# M103X.net
KiCad netlist of a schematic drawn in EAGLE
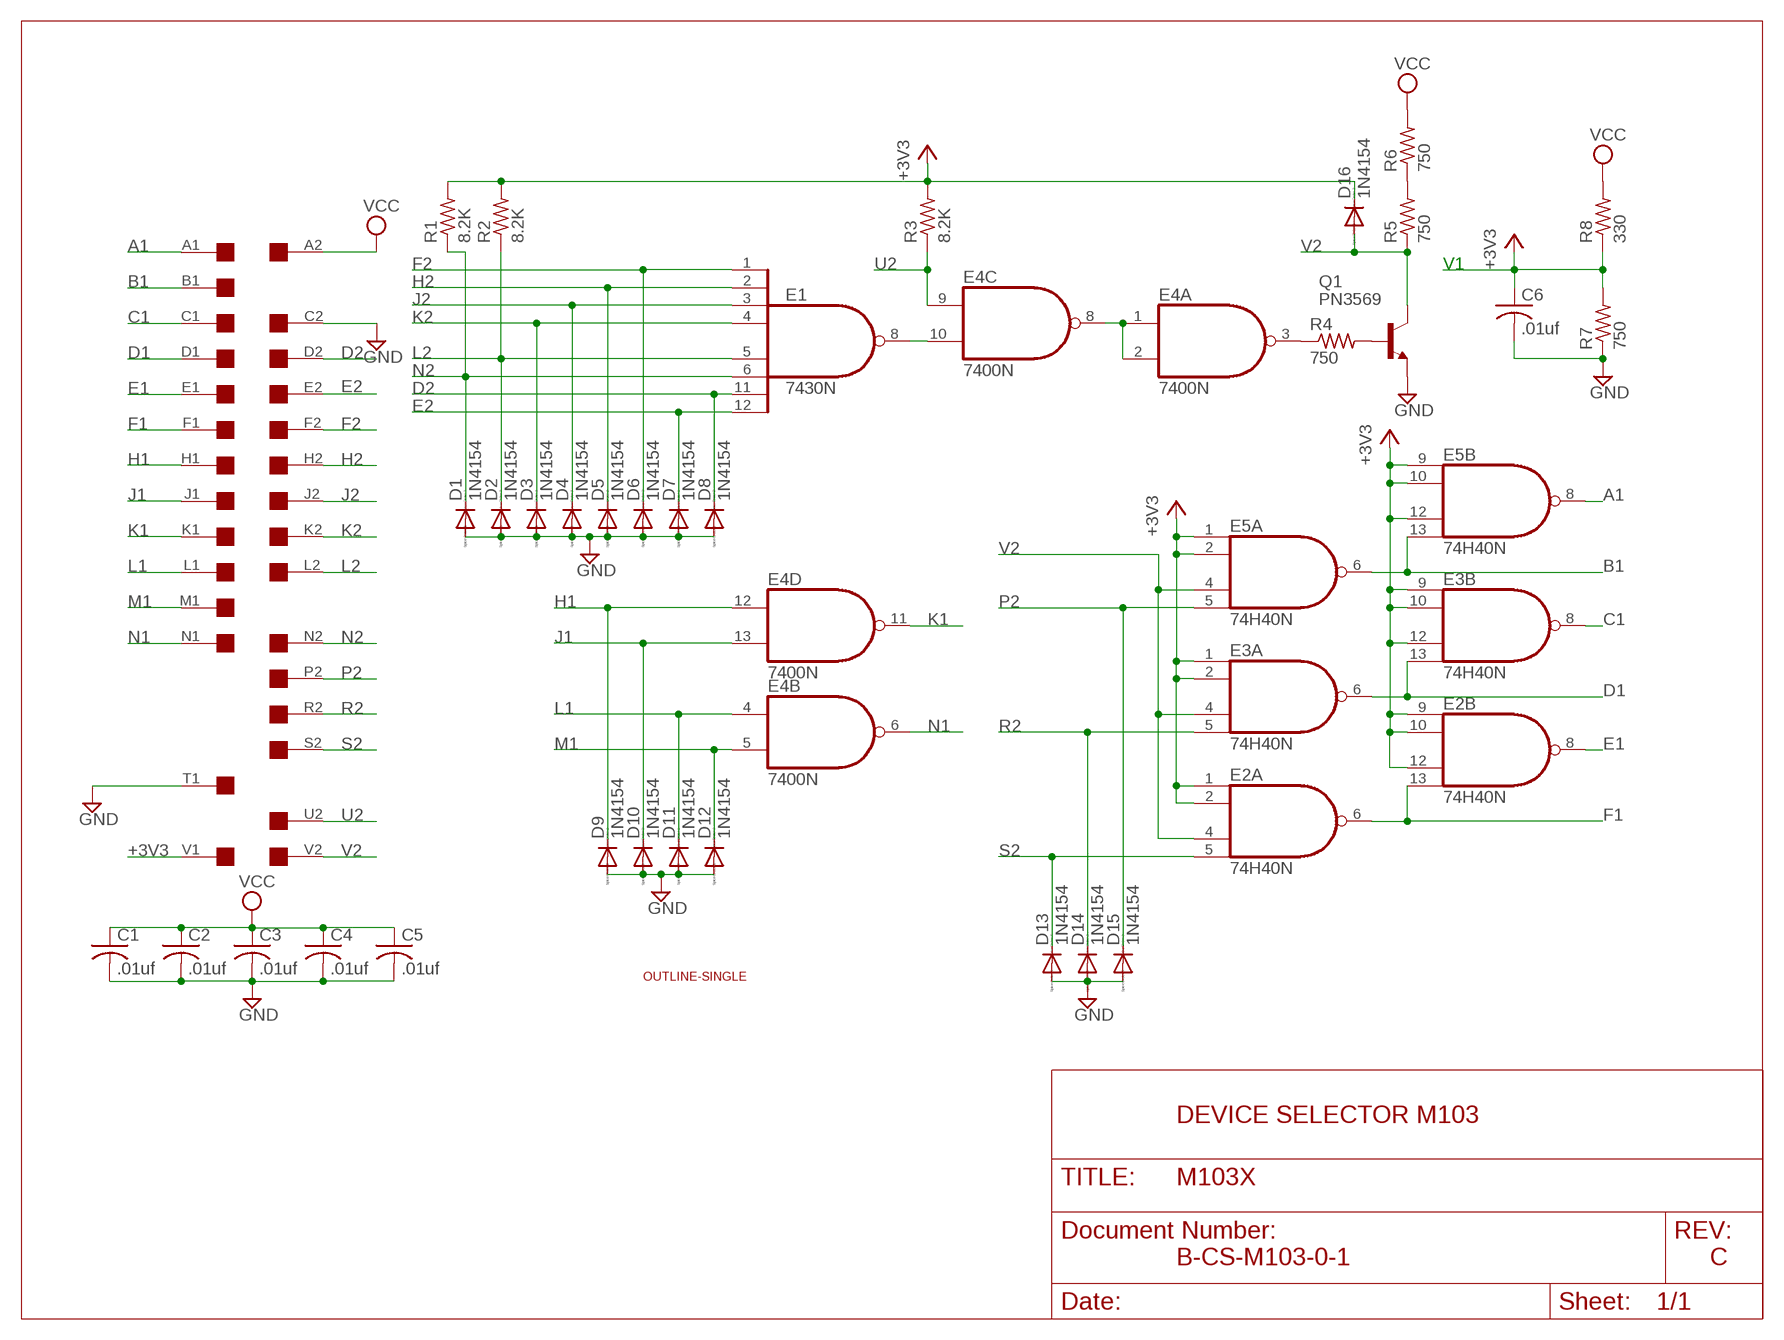
[diagram p0: schematic, sheet 1]

(export (version "E")
  (design (tool "Eeschema 10.0.6"))
  (components
    (comp (ref "C1")
      (value ".01uf")
      (footprint "eagle-import:C050-025X075")
      (libsource (lib "eagle-import") (part "C-US050-025X075"))
    )
    (comp (ref "C2")
      (value ".01uf")
      (footprint "eagle-import:C050-025X075")
      (libsource (lib "eagle-import") (part "C-US050-025X075"))
    )
    (comp (ref "C3")
      (value ".01uf")
      (footprint "eagle-import:C050-025X075")
      (libsource (lib "eagle-import") (part "C-US050-025X075"))
    )
    (comp (ref "C4")
      (value ".01uf")
      (footprint "eagle-import:C050-025X075")
      (libsource (lib "eagle-import") (part "C-US050-025X075"))
    )
    (comp (ref "C5")
      (value ".01uf")
      (footprint "eagle-import:C050-025X075")
      (libsource (lib "eagle-import") (part "C-US050-025X075"))
    )
    (comp (ref "C6")
      (value ".01uf")
      (footprint "eagle-import:C050-025X075")
      (libsource (lib "eagle-import") (part "C-US050-025X075"))
    )
    (comp (ref "D1")
      (value "1N4154")
      (footprint "eagle-import:DO35-10")
      (libsource (lib "eagle-import") (part "1N4148DO35-10"))
    )
    (comp (ref "D2")
      (value "1N4154")
      (footprint "eagle-import:DO35-10")
      (libsource (lib "eagle-import") (part "1N4148DO35-10"))
    )
    (comp (ref "D3")
      (value "1N4154")
      (footprint "eagle-import:DO35-10")
      (libsource (lib "eagle-import") (part "1N4148DO35-10"))
    )
    (comp (ref "D4")
      (value "1N4154")
      (footprint "eagle-import:DO35-10")
      (libsource (lib "eagle-import") (part "1N4148DO35-10"))
    )
    (comp (ref "D5")
      (value "1N4154")
      (footprint "eagle-import:DO35-10")
      (libsource (lib "eagle-import") (part "1N4148DO35-10"))
    )
    (comp (ref "D6")
      (value "1N4154")
      (footprint "eagle-import:DO35-10")
      (libsource (lib "eagle-import") (part "1N4148DO35-10"))
    )
    (comp (ref "D7")
      (value "1N4154")
      (footprint "eagle-import:DO35-10")
      (libsource (lib "eagle-import") (part "1N4148DO35-10"))
    )
    (comp (ref "D8")
      (value "1N4154")
      (footprint "eagle-import:DO35-10")
      (libsource (lib "eagle-import") (part "1N4148DO35-10"))
    )
    (comp (ref "D9")
      (value "1N4154")
      (footprint "eagle-import:DO35-10")
      (libsource (lib "eagle-import") (part "1N4148DO35-10"))
    )
    (comp (ref "D10")
      (value "1N4154")
      (footprint "eagle-import:DO35-10")
      (libsource (lib "eagle-import") (part "1N4148DO35-10"))
    )
    (comp (ref "D11")
      (value "1N4154")
      (footprint "eagle-import:DO35-10")
      (libsource (lib "eagle-import") (part "1N4148DO35-10"))
    )
    (comp (ref "D12")
      (value "1N4154")
      (footprint "eagle-import:DO35-10")
      (libsource (lib "eagle-import") (part "1N4148DO35-10"))
    )
    (comp (ref "D13")
      (value "1N4154")
      (footprint "eagle-import:DO35-10")
      (libsource (lib "eagle-import") (part "1N4148DO35-10"))
    )
    (comp (ref "D14")
      (value "1N4154")
      (footprint "eagle-import:DO35-10")
      (libsource (lib "eagle-import") (part "1N4148DO35-10"))
    )
    (comp (ref "D15")
      (value "1N4154")
      (footprint "eagle-import:DO35-10")
      (libsource (lib "eagle-import") (part "1N4148DO35-10"))
    )
    (comp (ref "D16")
      (value "1N4154")
      (footprint "eagle-import:DO35-10")
      (libsource (lib "eagle-import") (part "1N4148DO35-10"))
    )
    (comp (ref "E1")
      (value "7430N")
      (footprint "eagle-import:DIL14")
      (libsource (lib "eagle-import") (part "7430N"))
    )
    (comp (ref "E2")
      (value "74H40N")
      (footprint "eagle-import:DIL14")
      (libsource (lib "eagle-import") (part "7420NS"))
    )
    (comp (ref "E3")
      (value "74H40N")
      (footprint "eagle-import:DIL14")
      (libsource (lib "eagle-import") (part "7420NS"))
    )
    (comp (ref "E4")
      (value "7400N")
      (footprint "eagle-import:DIL14")
      (libsource (lib "eagle-import") (part "7400N"))
    )
    (comp (ref "E5")
      (value "74H40N")
      (footprint "eagle-import:DIL14")
      (libsource (lib "eagle-import") (part "7420NS"))
    )
    (comp (ref "Q1")
      (value "PN3569")
      (footprint "eagle-import:TO39")
      (libsource (lib "eagle-import") (part "-NPN-TO39-EBC2N1613"))
    )
    (comp (ref "R1")
      (value "8.2K")
      (footprint "eagle-import:0207_10")
      (libsource (lib "eagle-import") (part "R-US_0207/10"))
    )
    (comp (ref "R2")
      (value "8.2K")
      (footprint "eagle-import:0207_10")
      (libsource (lib "eagle-import") (part "R-US_0207/10"))
    )
    (comp (ref "R3")
      (value "8.2K")
      (footprint "eagle-import:0207_10")
      (libsource (lib "eagle-import") (part "R-US_0207/10"))
    )
    (comp (ref "R4")
      (value "750")
      (footprint "eagle-import:0207_10")
      (libsource (lib "eagle-import") (part "R-US_0207/10"))
    )
    (comp (ref "R5")
      (value "750")
      (footprint "eagle-import:0207_10")
      (libsource (lib "eagle-import") (part "R-US_0207/10"))
    )
    (comp (ref "R6")
      (value "750")
      (footprint "eagle-import:0207_10")
      (libsource (lib "eagle-import") (part "R-US_0207/10"))
    )
    (comp (ref "R7")
      (value "750")
      (footprint "eagle-import:0207_10")
      (libsource (lib "eagle-import") (part "R-US_0207/10"))
    )
    (comp (ref "R8")
      (value "330")
      (footprint "eagle-import:0207_10")
      (libsource (lib "eagle-import") (part "R-US_0207/10"))
    )
    (comp (ref "U$8")
      (value "SINGLE")
      (footprint "eagle-import:EDGE-CON2")
      (libsource (lib "eagle-import") (part "SINGLE"))
    )
    (comp (ref "U$9")
      (value "OUTLINE-SINGLE")
      (footprint "eagle-import:SINGLE")
      (libsource (lib "eagle-import") (part "OUTLINE-SINGLE"))
    )
  )
  (nets
    (net (code "1") (name "+3V3") (class "Default")
      (node (ref "C6") (pin "1") (pinfunction "1_1") (pintype "passive"))
      (node (ref "D16") (pin "C") (pinfunction "C_C") (pintype "passive"))
      (node (ref "E2") (pin "1") (pinfunction "I0_1") (pintype "input"))
      (node (ref "E2") (pin "10") (pinfunction "I1_10") (pintype "input"))
      (node (ref "E2") (pin "12") (pinfunction "I2_12") (pintype "input"))
      (node (ref "E2") (pin "2") (pinfunction "I1_2") (pintype "input"))
      (node (ref "E2") (pin "9") (pinfunction "I0_9") (pintype "input"))
      (node (ref "E3") (pin "1") (pinfunction "I0_1") (pintype "input"))
      (node (ref "E3") (pin "10") (pinfunction "I1_10") (pintype "input"))
      (node (ref "E3") (pin "12") (pinfunction "I2_12") (pintype "input"))
      (node (ref "E3") (pin "2") (pinfunction "I1_2") (pintype "input"))
      (node (ref "E3") (pin "9") (pinfunction "I0_9") (pintype "input"))
      (node (ref "E5") (pin "1") (pinfunction "I0_1") (pintype "input"))
      (node (ref "E5") (pin "10") (pinfunction "I1_10") (pintype "input"))
      (node (ref "E5") (pin "12") (pinfunction "I2_12") (pintype "input"))
      (node (ref "E5") (pin "2") (pinfunction "I1_2") (pintype "input"))
      (node (ref "E5") (pin "9") (pinfunction "I0_9") (pintype "input"))
      (node (ref "R1") (pin "2") (pinfunction "2_2") (pintype "passive"))
      (node (ref "R2") (pin "2") (pinfunction "2_2") (pintype "passive"))
      (node (ref "R3") (pin "2") (pinfunction "2_2") (pintype "passive"))
      (node (ref "R7") (pin "2") (pinfunction "2_2") (pintype "passive"))
      (node (ref "R8") (pin "1") (pinfunction "1_1") (pintype "passive"))
      (node (ref "U$8") (pin "V1") (pinfunction "1_V1") (pintype "bidirectional"))
    )
    (net (code "2") (name "/A1") (class "Default")
      (node (ref "E5") (pin "8") (pinfunction "O_8") (pintype "output"))
      (node (ref "U$8") (pin "A1") (pinfunction "1_A1") (pintype "bidirectional"))
    )
    (net (code "3") (name "/B1") (class "Default")
      (node (ref "E5") (pin "13") (pinfunction "I3_13") (pintype "input"))
      (node (ref "E5") (pin "6") (pinfunction "O_6") (pintype "output"))
      (node (ref "U$8") (pin "B1") (pinfunction "1_B1") (pintype "bidirectional"))
    )
    (net (code "4") (name "/C1") (class "Default")
      (node (ref "E3") (pin "8") (pinfunction "O_8") (pintype "output"))
      (node (ref "U$8") (pin "C1") (pinfunction "1_C1") (pintype "bidirectional"))
    )
    (net (code "5") (name "/D1") (class "Default")
      (node (ref "E3") (pin "13") (pinfunction "I3_13") (pintype "input"))
      (node (ref "E3") (pin "6") (pinfunction "O_6") (pintype "output"))
      (node (ref "U$8") (pin "D1") (pinfunction "1_D1") (pintype "bidirectional"))
    )
    (net (code "6") (name "/D2") (class "Default")
      (node (ref "D8") (pin "C") (pinfunction "C_C") (pintype "passive"))
      (node (ref "E1") (pin "11") (pinfunction "I6_11") (pintype "input"))
      (node (ref "U$8") (pin "D2") (pinfunction "1_D2") (pintype "bidirectional"))
    )
    (net (code "7") (name "/E1") (class "Default")
      (node (ref "E2") (pin "8") (pinfunction "O_8") (pintype "output"))
      (node (ref "U$8") (pin "E1") (pinfunction "1_E1") (pintype "bidirectional"))
    )
    (net (code "8") (name "/E2") (class "Default")
      (node (ref "D7") (pin "C") (pinfunction "C_C") (pintype "passive"))
      (node (ref "E1") (pin "12") (pinfunction "I7_12") (pintype "input"))
      (node (ref "U$8") (pin "E2") (pinfunction "1_E2") (pintype "bidirectional"))
    )
    (net (code "9") (name "/F1") (class "Default")
      (node (ref "E2") (pin "13") (pinfunction "I3_13") (pintype "input"))
      (node (ref "E2") (pin "6") (pinfunction "O_6") (pintype "output"))
      (node (ref "U$8") (pin "F1") (pinfunction "1_F1") (pintype "bidirectional"))
    )
    (net (code "10") (name "/F2") (class "Default")
      (node (ref "D6") (pin "C") (pinfunction "C_C") (pintype "passive"))
      (node (ref "E1") (pin "1") (pinfunction "I0_1") (pintype "input"))
      (node (ref "U$8") (pin "F2") (pinfunction "1_F2") (pintype "bidirectional"))
    )
    (net (code "11") (name "/H1") (class "Default")
      (node (ref "D9") (pin "C") (pinfunction "C_C") (pintype "passive"))
      (node (ref "E4") (pin "12") (pinfunction "I0_12") (pintype "input"))
      (node (ref "U$8") (pin "H1") (pinfunction "1_H1") (pintype "bidirectional"))
    )
    (net (code "12") (name "/H2") (class "Default")
      (node (ref "D5") (pin "C") (pinfunction "C_C") (pintype "passive"))
      (node (ref "E1") (pin "2") (pinfunction "I1_2") (pintype "input"))
      (node (ref "U$8") (pin "H2") (pinfunction "1_H2") (pintype "bidirectional"))
    )
    (net (code "13") (name "/J1") (class "Default")
      (node (ref "D10") (pin "C") (pinfunction "C_C") (pintype "passive"))
      (node (ref "E4") (pin "13") (pinfunction "I1_13") (pintype "input"))
      (node (ref "U$8") (pin "J1") (pinfunction "1_J1") (pintype "bidirectional"))
    )
    (net (code "14") (name "/J2") (class "Default")
      (node (ref "D4") (pin "C") (pinfunction "C_C") (pintype "passive"))
      (node (ref "E1") (pin "3") (pinfunction "I2_3") (pintype "input"))
      (node (ref "U$8") (pin "J2") (pinfunction "1_J2") (pintype "bidirectional"))
    )
    (net (code "15") (name "/K1") (class "Default")
      (node (ref "E4") (pin "11") (pinfunction "O_11") (pintype "output"))
      (node (ref "U$8") (pin "K1") (pinfunction "1_K1") (pintype "bidirectional"))
    )
    (net (code "16") (name "/K2") (class "Default")
      (node (ref "D3") (pin "C") (pinfunction "C_C") (pintype "passive"))
      (node (ref "E1") (pin "4") (pinfunction "I3_4") (pintype "input"))
      (node (ref "U$8") (pin "K2") (pinfunction "1_K2") (pintype "bidirectional"))
    )
    (net (code "17") (name "/L1") (class "Default")
      (node (ref "D11") (pin "C") (pinfunction "C_C") (pintype "passive"))
      (node (ref "E4") (pin "4") (pinfunction "I0_4") (pintype "input"))
      (node (ref "U$8") (pin "L1") (pinfunction "1_L1") (pintype "bidirectional"))
    )
    (net (code "18") (name "/L2") (class "Default")
      (node (ref "D2") (pin "C") (pinfunction "C_C") (pintype "passive"))
      (node (ref "E1") (pin "5") (pinfunction "I4_5") (pintype "input"))
      (node (ref "R2") (pin "1") (pinfunction "1_1") (pintype "passive"))
      (node (ref "U$8") (pin "L2") (pinfunction "1_L2") (pintype "bidirectional"))
    )
    (net (code "19") (name "/M1") (class "Default")
      (node (ref "D12") (pin "C") (pinfunction "C_C") (pintype "passive"))
      (node (ref "E4") (pin "5") (pinfunction "I1_5") (pintype "input"))
      (node (ref "U$8") (pin "M1") (pinfunction "1_M1") (pintype "bidirectional"))
    )
    (net (code "20") (name "/N1") (class "Default")
      (node (ref "E4") (pin "6") (pinfunction "O_6") (pintype "output"))
      (node (ref "U$8") (pin "N1") (pinfunction "1_N1") (pintype "bidirectional"))
    )
    (net (code "21") (name "/N2") (class "Default")
      (node (ref "D1") (pin "C") (pinfunction "C_C") (pintype "passive"))
      (node (ref "E1") (pin "6") (pinfunction "I5_6") (pintype "input"))
      (node (ref "R1") (pin "1") (pinfunction "1_1") (pintype "passive"))
      (node (ref "U$8") (pin "N2") (pinfunction "1_N2") (pintype "bidirectional"))
    )
    (net (code "22") (name "/P2") (class "Default")
      (node (ref "D15") (pin "C") (pinfunction "C_C") (pintype "passive"))
      (node (ref "E5") (pin "5") (pinfunction "I3_5") (pintype "input"))
      (node (ref "U$8") (pin "P2") (pinfunction "1_P2") (pintype "bidirectional"))
    )
    (net (code "23") (name "/R2") (class "Default")
      (node (ref "D14") (pin "C") (pinfunction "C_C") (pintype "passive"))
      (node (ref "E3") (pin "5") (pinfunction "I3_5") (pintype "input"))
      (node (ref "U$8") (pin "R2") (pinfunction "1_R2") (pintype "bidirectional"))
    )
    (net (code "24") (name "/S2") (class "Default")
      (node (ref "D13") (pin "C") (pinfunction "C_C") (pintype "passive"))
      (node (ref "E2") (pin "5") (pinfunction "I3_5") (pintype "input"))
      (node (ref "U$8") (pin "S2") (pinfunction "1_S2") (pintype "bidirectional"))
    )
    (net (code "25") (name "/U2") (class "Default")
      (node (ref "E4") (pin "9") (pinfunction "I0_9") (pintype "input"))
      (node (ref "R3") (pin "1") (pinfunction "1_1") (pintype "passive"))
      (node (ref "U$8") (pin "U2") (pinfunction "1_U2") (pintype "bidirectional"))
    )
    (net (code "26") (name "/V2") (class "Default")
      (node (ref "D16") (pin "A") (pinfunction "A_A") (pintype "passive"))
      (node (ref "E2") (pin "4") (pinfunction "I2_4") (pintype "input"))
      (node (ref "E3") (pin "4") (pinfunction "I2_4") (pintype "input"))
      (node (ref "E5") (pin "4") (pinfunction "I2_4") (pintype "input"))
      (node (ref "Q1") (pin "3") (pinfunction "C_3") (pintype "passive"))
      (node (ref "R5") (pin "1") (pinfunction "1_1") (pintype "passive"))
      (node (ref "U$8") (pin "V2") (pinfunction "1_V2") (pintype "bidirectional"))
    )
    (net (code "27") (name "GND") (class "Default")
      (node (ref "C1") (pin "2") (pinfunction "2_2") (pintype "passive"))
      (node (ref "C2") (pin "2") (pinfunction "2_2") (pintype "passive"))
      (node (ref "C3") (pin "2") (pinfunction "2_2") (pintype "passive"))
      (node (ref "C4") (pin "2") (pinfunction "2_2") (pintype "passive"))
      (node (ref "C5") (pin "2") (pinfunction "2_2") (pintype "passive"))
      (node (ref "C6") (pin "2") (pinfunction "2_2") (pintype "passive"))
      (node (ref "D1") (pin "A") (pinfunction "A_A") (pintype "passive"))
      (node (ref "D10") (pin "A") (pinfunction "A_A") (pintype "passive"))
      (node (ref "D11") (pin "A") (pinfunction "A_A") (pintype "passive"))
      (node (ref "D12") (pin "A") (pinfunction "A_A") (pintype "passive"))
      (node (ref "D13") (pin "A") (pinfunction "A_A") (pintype "passive"))
      (node (ref "D14") (pin "A") (pinfunction "A_A") (pintype "passive"))
      (node (ref "D15") (pin "A") (pinfunction "A_A") (pintype "passive"))
      (node (ref "D2") (pin "A") (pinfunction "A_A") (pintype "passive"))
      (node (ref "D3") (pin "A") (pinfunction "A_A") (pintype "passive"))
      (node (ref "D4") (pin "A") (pinfunction "A_A") (pintype "passive"))
      (node (ref "D5") (pin "A") (pinfunction "A_A") (pintype "passive"))
      (node (ref "D6") (pin "A") (pinfunction "A_A") (pintype "passive"))
      (node (ref "D7") (pin "A") (pinfunction "A_A") (pintype "passive"))
      (node (ref "D8") (pin "A") (pinfunction "A_A") (pintype "passive"))
      (node (ref "D9") (pin "A") (pinfunction "A_A") (pintype "passive"))
      (node (ref "Q1") (pin "1") (pinfunction "E_1") (pintype "passive"))
      (node (ref "R7") (pin "1") (pinfunction "1_1") (pintype "passive"))
      (node (ref "U$8") (pin "C2") (pinfunction "1_C2") (pintype "bidirectional"))
      (node (ref "U$8") (pin "T1") (pinfunction "1_T1") (pintype "bidirectional"))
    )
    (net (code "28") (name "Net-(E1A-O)") (class "Default")
      (node (ref "E1") (pin "8") (pinfunction "O_8") (pintype "output"))
      (node (ref "E4") (pin "10") (pinfunction "I1_10") (pintype "input"))
    )
    (net (code "29") (name "Net-(E4A-I0)") (class "Default")
      (node (ref "E4") (pin "1") (pinfunction "I0_1") (pintype "input"))
      (node (ref "E4") (pin "2") (pinfunction "I1_2") (pintype "input"))
      (node (ref "E4") (pin "8") (pinfunction "O_8") (pintype "output"))
    )
    (net (code "30") (name "Net-(E4A-O)") (class "Default")
      (node (ref "E4") (pin "3") (pinfunction "O_3") (pintype "output"))
      (node (ref "R4") (pin "1") (pinfunction "1_1") (pintype "passive"))
    )
    (net (code "31") (name "Net-(Q1-B)") (class "Default")
      (node (ref "Q1") (pin "2") (pinfunction "B_2") (pintype "passive"))
      (node (ref "R4") (pin "2") (pinfunction "2_2") (pintype "passive"))
    )
    (net (code "32") (name "Net-(R5-Pad2)") (class "Default")
      (node (ref "R5") (pin "2") (pinfunction "2_2") (pintype "passive"))
      (node (ref "R6") (pin "1") (pinfunction "1_1") (pintype "passive"))
    )
    (net (code "33") (name "VCC") (class "Default")
      (node (ref "C1") (pin "1") (pinfunction "1_1") (pintype "passive"))
      (node (ref "C2") (pin "1") (pinfunction "1_1") (pintype "passive"))
      (node (ref "C3") (pin "1") (pinfunction "1_1") (pintype "passive"))
      (node (ref "C4") (pin "1") (pinfunction "1_1") (pintype "passive"))
      (node (ref "C5") (pin "1") (pinfunction "1_1") (pintype "passive"))
      (node (ref "R6") (pin "2") (pinfunction "2_2") (pintype "passive"))
      (node (ref "R8") (pin "2") (pinfunction "2_2") (pintype "passive"))
      (node (ref "U$8") (pin "A2") (pinfunction "1_A2") (pintype "bidirectional"))
    )
  )
)
